# G1Tech-MAX31855K_v01.net
KiCad netlist of a schematic drawn in EAGLE
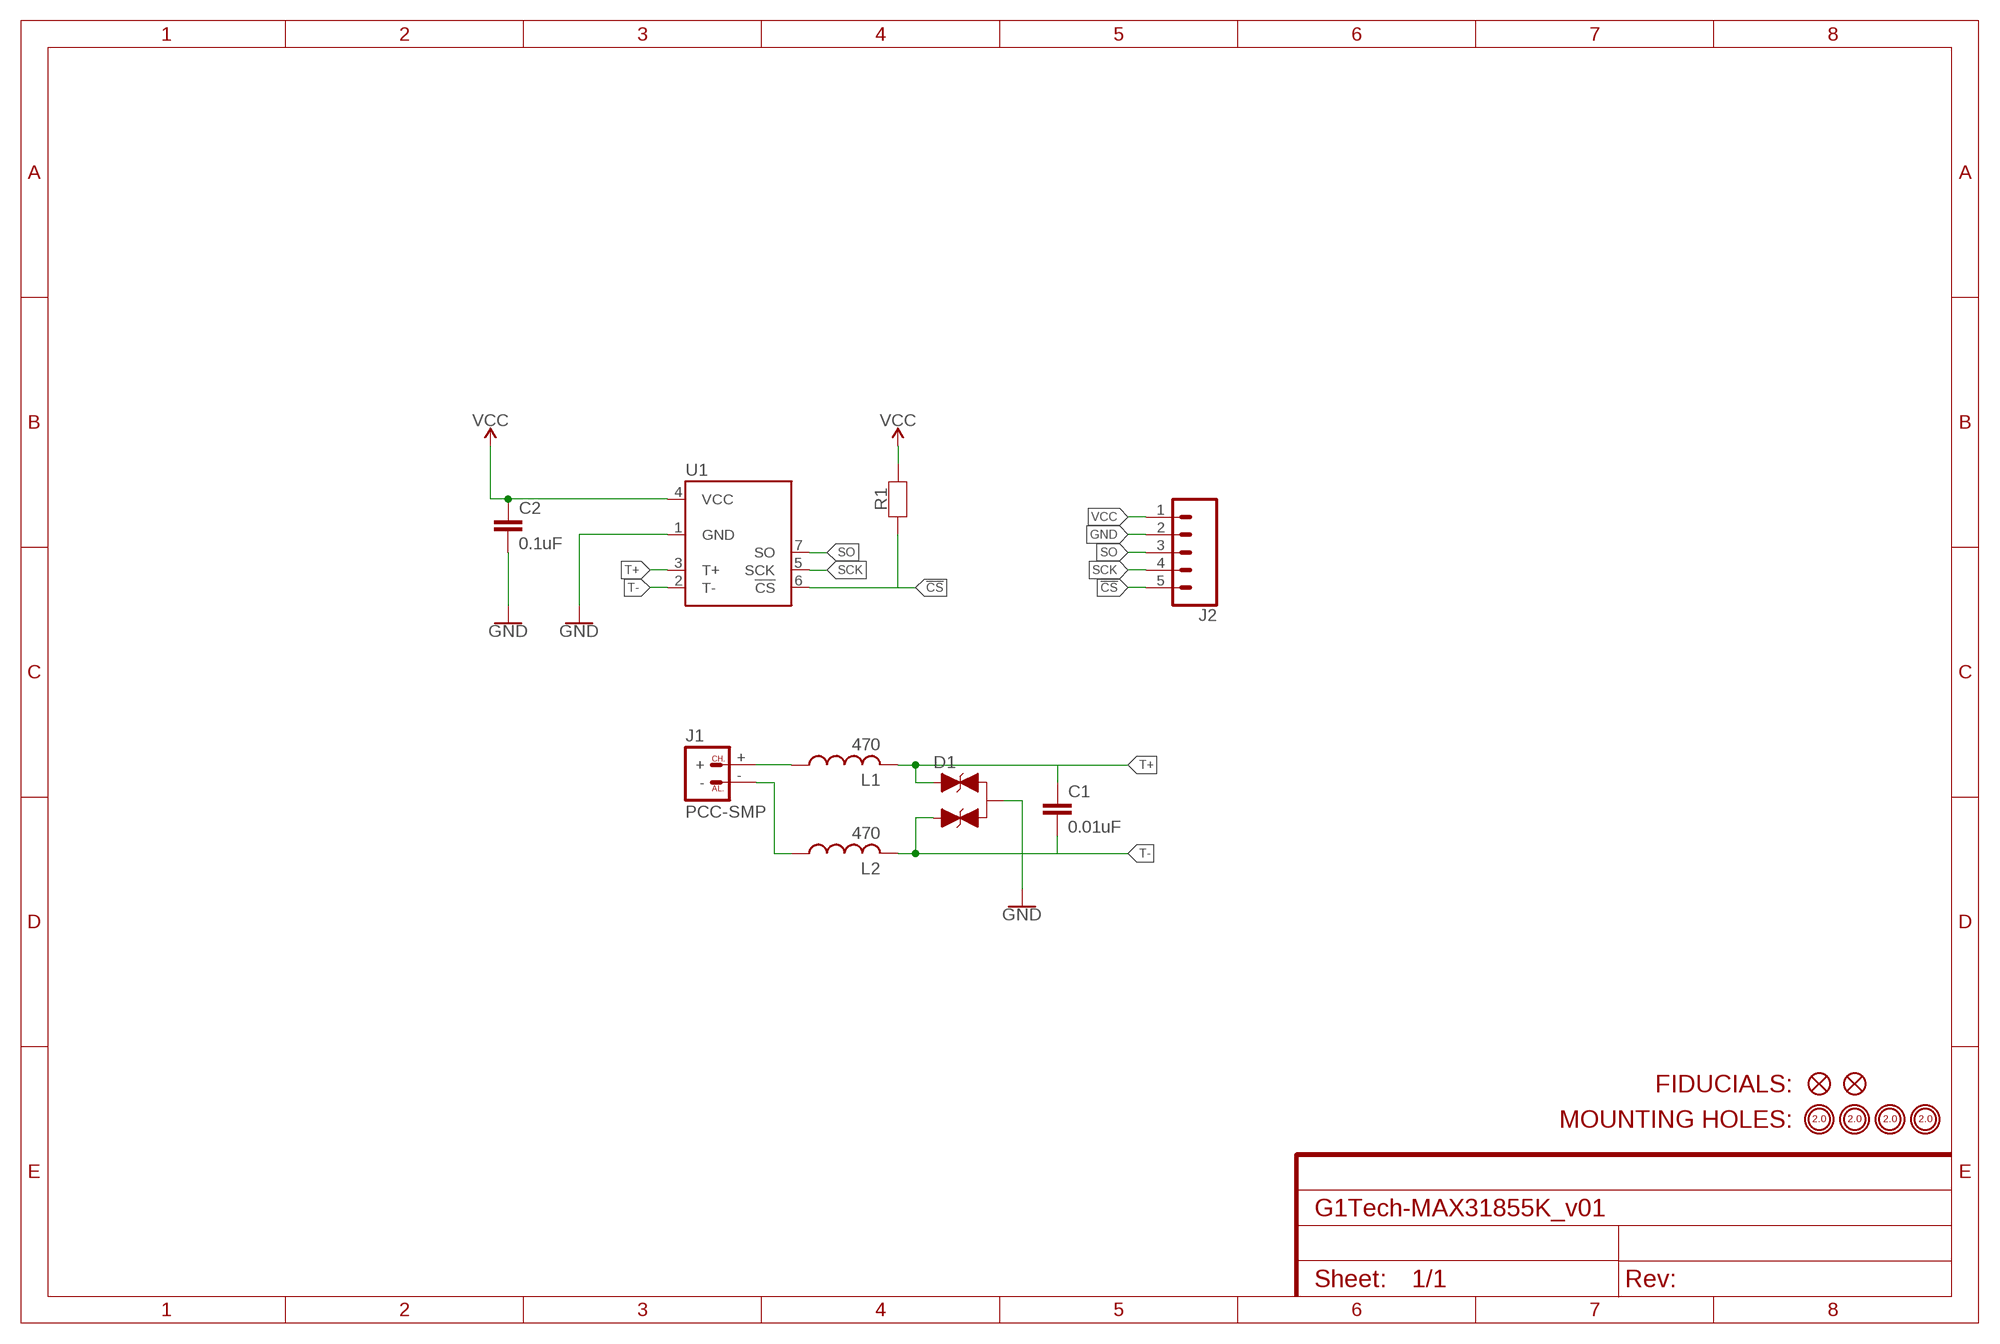
[diagram p0: schematic, sheet 1]

(export (version "E")
  (design (tool "Eeschema 10.0.6"))
  (components
    (comp (ref "C1")
      (value "0.01uF")
      (footprint "eagle-import:C0603")
      (libsource (lib "eagle-import") (part "C0603"))
    )
    (comp (ref "C2")
      (value "0.1uF")
      (footprint "eagle-import:C0603")
      (libsource (lib "eagle-import") (part "C0603"))
    )
    (comp (ref "D1")
      (value "DIODE-TVS-NUP2105L")
      (footprint "eagle-import:SOT23-3")
      (libsource (lib "eagle-import") (part "DIODE-TVS-NUP2105L"))
    )
    (comp (ref "FD1")
      (value "FIDUCIAL-1X2")
      (footprint "eagle-import:FIDUCIAL-1X2")
      (libsource (lib "eagle-import") (part "FIDUCIAL-1X2"))
    )
    (comp (ref "FD2")
      (value "FIDUCIAL-1X2")
      (footprint "eagle-import:FIDUCIAL-1X2")
      (libsource (lib "eagle-import") (part "FIDUCIAL-1X2"))
    )
    (comp (ref "H1")
      (value "MOUNTINGHOLE-PLATED-2.0")
      (footprint "eagle-import:MOUNTINGHOLE-PLATED-2.0")
      (libsource (lib "eagle-import") (part "MOUNTINGHOLE-PLATED-2.0"))
    )
    (comp (ref "H2")
      (value "MOUNTINGHOLE-PLATED-2.0")
      (footprint "eagle-import:MOUNTINGHOLE-PLATED-2.0")
      (libsource (lib "eagle-import") (part "MOUNTINGHOLE-PLATED-2.0"))
    )
    (comp (ref "H3")
      (value "MOUNTINGHOLE-PLATED-2.0")
      (footprint "eagle-import:MOUNTINGHOLE-PLATED-2.0")
      (libsource (lib "eagle-import") (part "MOUNTINGHOLE-PLATED-2.0"))
    )
    (comp (ref "H4")
      (value "MOUNTINGHOLE-PLATED-2.0")
      (footprint "eagle-import:MOUNTINGHOLE-PLATED-2.0")
      (libsource (lib "eagle-import") (part "MOUNTINGHOLE-PLATED-2.0"))
    )
    (comp (ref "J1")
      (value "PCC-SMP")
      (footprint "eagle-import:PCC-SMP")
      (libsource (lib "eagle-import") (part "PCC-SMP"))
    )
    (comp (ref "J2")
      (value "CONN-1X5")
      (footprint "eagle-import:1X05_NO_SILK")
      (libsource (lib "eagle-import") (part "CONN-1X5"))
    )
    (comp (ref "L1")
      (value "470")
      (footprint "eagle-import:MURATA-L0603")
      (libsource (lib "eagle-import") (part "FERRITE-BEADS-BLM18PG471SN1D"))
    )
    (comp (ref "L2")
      (value "470")
      (footprint "eagle-import:MURATA-L0603")
      (libsource (lib "eagle-import") (part "FERRITE-BEADS-BLM18PG471SN1D"))
    )
    (comp (ref "R1")
      (value "YAGEO-R0603")
      (footprint "eagle-import:YAGEO-R0603")
      (libsource (lib "eagle-import") (part "YAGEO-R0603"))
    )
    (comp (ref "U1")
      (value "MAX31855KASA+")
      (footprint "eagle-import:SO08")
      (libsource (lib "eagle-import") (part "MAX31855KASA+"))
    )
  )
  (nets
    (net (code "1") (name "/~{CS}") (class "Default")
      (node (ref "J2") (pin "5") (pinfunction "5_5") (pintype "passive"))
      (node (ref "R1") (pin "1") (pinfunction "1_1") (pintype "passive"))
      (node (ref "U1") (pin "6") (pinfunction "~{CS}_6") (pintype "bidirectional"))
    )
    (net (code "2") (name "GND") (class "Default")
      (node (ref "C2") (pin "2") (pinfunction "2_2") (pintype "passive"))
      (node (ref "D1") (pin "3") (pinfunction "3_3") (pintype "passive"))
      (node (ref "J2") (pin "2") (pinfunction "2_2") (pintype "passive"))
      (node (ref "U1") (pin "1") (pinfunction "GND_1") (pintype "power_in"))
    )
    (net (code "3") (name "Net-(J1-Pad+)") (class "Default")
      (node (ref "J1") (pin "+") (pinfunction "+_+") (pintype "passive"))
      (node (ref "L1") (pin "1") (pinfunction "1_1") (pintype "passive"))
    )
    (net (code "4") (name "Net-(J1-Pad-)") (class "Default")
      (node (ref "J1") (pin "-") (pinfunction "-_-") (pintype "passive"))
      (node (ref "L2") (pin "1") (pinfunction "1_1") (pintype "passive"))
    )
    (net (code "5") (name "SCK") (class "Default")
      (node (ref "J2") (pin "4") (pinfunction "4_4") (pintype "passive"))
      (node (ref "U1") (pin "5") (pinfunction "SCK_5") (pintype "bidirectional"))
    )
    (net (code "6") (name "SO") (class "Default")
      (node (ref "J2") (pin "3") (pinfunction "3_3") (pintype "passive"))
      (node (ref "U1") (pin "7") (pinfunction "SO_7") (pintype "bidirectional"))
    )
    (net (code "7") (name "T+") (class "Default")
      (node (ref "C1") (pin "1") (pinfunction "1_1") (pintype "passive"))
      (node (ref "D1") (pin "1") (pinfunction "1_1") (pintype "passive"))
      (node (ref "L1") (pin "2") (pinfunction "2_2") (pintype "passive"))
      (node (ref "U1") (pin "3") (pinfunction "T+_3") (pintype "bidirectional"))
    )
    (net (code "8") (name "T-") (class "Default")
      (node (ref "C1") (pin "2") (pinfunction "2_2") (pintype "passive"))
      (node (ref "D1") (pin "2") (pinfunction "2_2") (pintype "passive"))
      (node (ref "L2") (pin "2") (pinfunction "2_2") (pintype "passive"))
      (node (ref "U1") (pin "2") (pinfunction "T-_2") (pintype "bidirectional"))
    )
    (net (code "9") (name "VCC") (class "Default")
      (node (ref "C2") (pin "1") (pinfunction "1_1") (pintype "passive"))
      (node (ref "J2") (pin "1") (pinfunction "1_1") (pintype "passive"))
      (node (ref "R1") (pin "2") (pinfunction "2_2") (pintype "passive"))
      (node (ref "U1") (pin "4") (pinfunction "VCC_4") (pintype "power_in"))
    )
  )
)
